# 8bitLineSensor.net
KiCad netlist of a schematic drawn in EAGLE
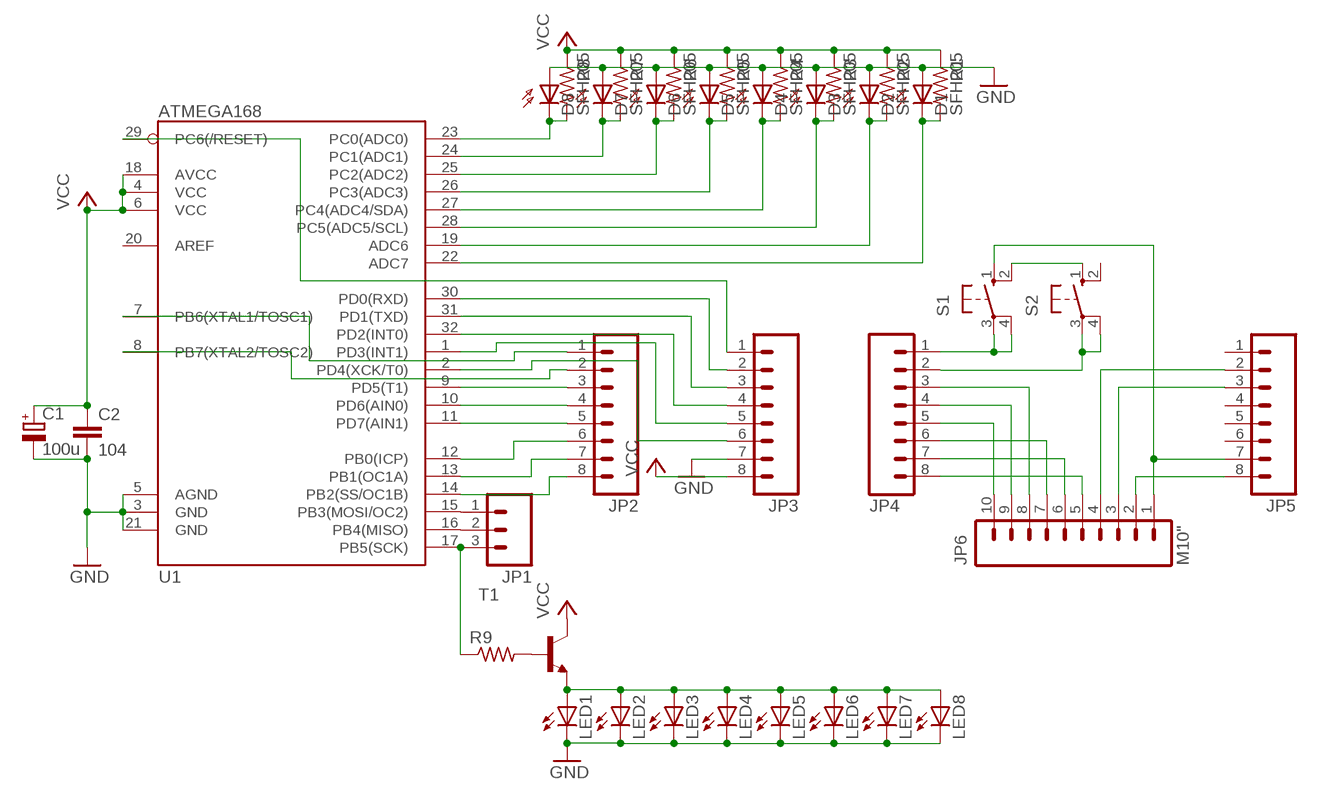
[diagram p0: schematic, sheet 1]

(export (version "E")
  (design (tool "Eeschema 10.0.6"))
  (components
    (comp (ref "C1")
      (value "100u")
      (footprint "eagle-import:E2,5-7")
      (libsource (lib "eagle-import") (part "CPOL-EUE2.5-7"))
    )
    (comp (ref "C2")
      (value "104")
      (footprint "eagle-import:C0805")
      (libsource (lib "eagle-import") (part "C-EUC0805"))
    )
    (comp (ref "D1")
      (value "SFH205")
      (footprint "eagle-import:SFH205")
      (libsource (lib "eagle-import") (part "SFH205"))
    )
    (comp (ref "D2")
      (value "SFH205")
      (footprint "eagle-import:SFH205")
      (libsource (lib "eagle-import") (part "SFH205"))
    )
    (comp (ref "D3")
      (value "SFH205")
      (footprint "eagle-import:SFH205")
      (libsource (lib "eagle-import") (part "SFH205"))
    )
    (comp (ref "D4")
      (value "SFH205")
      (footprint "eagle-import:SFH205")
      (libsource (lib "eagle-import") (part "SFH205"))
    )
    (comp (ref "D5")
      (value "SFH205")
      (footprint "eagle-import:SFH205")
      (libsource (lib "eagle-import") (part "SFH205"))
    )
    (comp (ref "D6")
      (value "SFH205")
      (footprint "eagle-import:SFH205")
      (libsource (lib "eagle-import") (part "SFH205"))
    )
    (comp (ref "D7")
      (value "SFH205")
      (footprint "eagle-import:SFH205")
      (libsource (lib "eagle-import") (part "SFH205"))
    )
    (comp (ref "D8")
      (value "SFH205")
      (footprint "eagle-import:SFH205")
      (libsource (lib "eagle-import") (part "SFH205"))
    )
    (comp (ref "JP1")
      (value "M03PTH")
      (footprint "eagle-import:1X03")
      (libsource (lib "eagle-import") (part "M03PTH"))
    )
    (comp (ref "JP2")
      (value "M08")
      (footprint "eagle-import:1X08")
      (libsource (lib "eagle-import") (part "M08"))
    )
    (comp (ref "JP3")
      (value "M08")
      (footprint "eagle-import:1X08")
      (libsource (lib "eagle-import") (part "M08"))
    )
    (comp (ref "JP4")
      (value "M08")
      (footprint "eagle-import:1X08")
      (libsource (lib "eagle-import") (part "M08"))
    )
    (comp (ref "JP5")
      (value "M08")
      (footprint "eagle-import:1X08")
      (libsource (lib "eagle-import") (part "M08"))
    )
    (comp (ref "JP6")
      (value "M10\"")
      (footprint "eagle-import:1X10")
      (libsource (lib "eagle-import") (part "M10{dblquote}"))
    )
    (comp (ref "LED1")
      (value "LED5MM")
      (footprint "eagle-import:LED5MM")
      (libsource (lib "eagle-import") (part "LED5MM"))
    )
    (comp (ref "LED2")
      (value "LED5MM")
      (footprint "eagle-import:LED5MM")
      (libsource (lib "eagle-import") (part "LED5MM"))
    )
    (comp (ref "LED3")
      (value "LED5MM")
      (footprint "eagle-import:LED5MM")
      (libsource (lib "eagle-import") (part "LED5MM"))
    )
    (comp (ref "LED4")
      (value "LED5MM")
      (footprint "eagle-import:LED5MM")
      (libsource (lib "eagle-import") (part "LED5MM"))
    )
    (comp (ref "LED5")
      (value "LED5MM")
      (footprint "eagle-import:LED5MM")
      (libsource (lib "eagle-import") (part "LED5MM"))
    )
    (comp (ref "LED6")
      (value "LED5MM")
      (footprint "eagle-import:LED5MM")
      (libsource (lib "eagle-import") (part "LED5MM"))
    )
    (comp (ref "LED7")
      (value "LED5MM")
      (footprint "eagle-import:LED5MM")
      (libsource (lib "eagle-import") (part "LED5MM"))
    )
    (comp (ref "LED8")
      (value "LED5MM")
      (footprint "eagle-import:LED5MM")
      (libsource (lib "eagle-import") (part "LED5MM"))
    )
    (comp (ref "R1")
      (value "R-US_R0805")
      (footprint "eagle-import:R0805")
      (libsource (lib "eagle-import") (part "R-US_R0805"))
    )
    (comp (ref "R2")
      (value "R-US_R0805")
      (footprint "eagle-import:R0805")
      (libsource (lib "eagle-import") (part "R-US_R0805"))
    )
    (comp (ref "R3")
      (value "R-US_R0805")
      (footprint "eagle-import:R0805")
      (libsource (lib "eagle-import") (part "R-US_R0805"))
    )
    (comp (ref "R4")
      (value "R-US_R0805")
      (footprint "eagle-import:R0805")
      (libsource (lib "eagle-import") (part "R-US_R0805"))
    )
    (comp (ref "R5")
      (value "R-US_R0805")
      (footprint "eagle-import:R0805")
      (libsource (lib "eagle-import") (part "R-US_R0805"))
    )
    (comp (ref "R6")
      (value "R-US_R0805")
      (footprint "eagle-import:R0805")
      (libsource (lib "eagle-import") (part "R-US_R0805"))
    )
    (comp (ref "R7")
      (value "R-US_R0805")
      (footprint "eagle-import:R0805")
      (libsource (lib "eagle-import") (part "R-US_R0805"))
    )
    (comp (ref "R8")
      (value "R-US_R0805")
      (footprint "eagle-import:R0805")
      (libsource (lib "eagle-import") (part "R-US_R0805"))
    )
    (comp (ref "R9")
      (value "R-US_R0805")
      (footprint "eagle-import:R0805")
      (libsource (lib "eagle-import") (part "R-US_R0805"))
    )
    (comp (ref "S1")
      (value "10-XX")
      (footprint "eagle-import:B3F-10XX")
      (fields (field (name "MPN") "B3F-1000"))
      (libsource (lib "eagle-import") (part "10-XX"))
    )
    (comp (ref "S2")
      (value "10-XX")
      (footprint "eagle-import:B3F-10XX")
      (fields (field (name "MPN") "B3F-1000"))
      (libsource (lib "eagle-import") (part "10-XX"))
    )
    (comp (ref "T1")
      (value "MMBT2222ALT1-NPN-SOT23-BEC")
      (footprint "eagle-import:SOT23-BEC")
      (libsource (lib "eagle-import") (part "-NPN-SOT23-BECMMBT2222ALT1"))
    )
    (comp (ref "U1")
      (value "ATMEGA168")
      (footprint "eagle-import:TQFP32-08")
      (libsource (lib "eagle-import") (part "ATMEGA168"))
    )
  )
  (nets
    (net (code "1") (name "GND") (class "Default")
      (node (ref "C1") (pin "-") (pinfunction "-_-") (pintype "passive"))
      (node (ref "C2") (pin "2") (pinfunction "2_2") (pintype "passive"))
      (node (ref "D1") (pin "A") (pinfunction "A_A") (pintype "passive"))
      (node (ref "D2") (pin "A") (pinfunction "A_A") (pintype "passive"))
      (node (ref "D3") (pin "A") (pinfunction "A_A") (pintype "passive"))
      (node (ref "D4") (pin "A") (pinfunction "A_A") (pintype "passive"))
      (node (ref "D5") (pin "A") (pinfunction "A_A") (pintype "passive"))
      (node (ref "D6") (pin "A") (pinfunction "A_A") (pintype "passive"))
      (node (ref "D7") (pin "A") (pinfunction "A_A") (pintype "passive"))
      (node (ref "D8") (pin "A") (pinfunction "A_A") (pintype "passive"))
      (node (ref "JP3") (pin "7") (pinfunction "7_7") (pintype "passive"))
      (node (ref "LED1") (pin "K") (pinfunction "C_K") (pintype "passive"))
      (node (ref "LED2") (pin "K") (pinfunction "C_K") (pintype "passive"))
      (node (ref "LED3") (pin "K") (pinfunction "C_K") (pintype "passive"))
      (node (ref "LED4") (pin "K") (pinfunction "C_K") (pintype "passive"))
      (node (ref "LED5") (pin "K") (pinfunction "C_K") (pintype "passive"))
      (node (ref "LED6") (pin "K") (pinfunction "C_K") (pintype "passive"))
      (node (ref "LED7") (pin "K") (pinfunction "C_K") (pintype "passive"))
      (node (ref "LED8") (pin "K") (pinfunction "C_K") (pintype "passive"))
      (node (ref "U1") (pin "21") (pinfunction "GND_21") (pintype "bidirectional"))
      (node (ref "U1") (pin "3") (pinfunction "GND_3") (pintype "bidirectional"))
      (node (ref "U1") (pin "5") (pinfunction "AGND_5") (pintype "bidirectional"))
    )
    (net (code "2") (name "Net-(D1-C)") (class "Default")
      (node (ref "D1") (pin "K") (pinfunction "C_K") (pintype "passive"))
      (node (ref "R1") (pin "2") (pinfunction "2_2") (pintype "passive"))
      (node (ref "U1") (pin "22") (pinfunction "ADC7_22") (pintype "bidirectional"))
    )
    (net (code "3") (name "Net-(D2-C)") (class "Default")
      (node (ref "D2") (pin "K") (pinfunction "C_K") (pintype "passive"))
      (node (ref "R2") (pin "2") (pinfunction "2_2") (pintype "passive"))
      (node (ref "U1") (pin "19") (pinfunction "ADC6_19") (pintype "bidirectional"))
    )
    (net (code "4") (name "Net-(D3-C)") (class "Default")
      (node (ref "D3") (pin "K") (pinfunction "C_K") (pintype "passive"))
      (node (ref "R3") (pin "2") (pinfunction "2_2") (pintype "passive"))
      (node (ref "U1") (pin "28") (pinfunction "PC5(ADC5/SCL)_28") (pintype "bidirectional"))
    )
    (net (code "5") (name "Net-(D4-C)") (class "Default")
      (node (ref "D4") (pin "K") (pinfunction "C_K") (pintype "passive"))
      (node (ref "R4") (pin "2") (pinfunction "2_2") (pintype "passive"))
      (node (ref "U1") (pin "27") (pinfunction "PC4(ADC4/SDA)_27") (pintype "bidirectional"))
    )
    (net (code "6") (name "Net-(D5-C)") (class "Default")
      (node (ref "D5") (pin "K") (pinfunction "C_K") (pintype "passive"))
      (node (ref "R5") (pin "2") (pinfunction "2_2") (pintype "passive"))
      (node (ref "U1") (pin "26") (pinfunction "PC3(ADC3)_26") (pintype "bidirectional"))
    )
    (net (code "7") (name "Net-(D6-C)") (class "Default")
      (node (ref "D6") (pin "K") (pinfunction "C_K") (pintype "passive"))
      (node (ref "R6") (pin "2") (pinfunction "2_2") (pintype "passive"))
      (node (ref "U1") (pin "25") (pinfunction "PC2(ADC2)_25") (pintype "bidirectional"))
    )
    (net (code "8") (name "Net-(D7-C)") (class "Default")
      (node (ref "D7") (pin "K") (pinfunction "C_K") (pintype "passive"))
      (node (ref "R7") (pin "2") (pinfunction "2_2") (pintype "passive"))
      (node (ref "U1") (pin "24") (pinfunction "PC1(ADC1)_24") (pintype "bidirectional"))
    )
    (net (code "9") (name "Net-(D8-C)") (class "Default")
      (node (ref "D8") (pin "K") (pinfunction "C_K") (pintype "passive"))
      (node (ref "R8") (pin "2") (pinfunction "2_2") (pintype "passive"))
      (node (ref "U1") (pin "23") (pinfunction "PC0(ADC0)_23") (pintype "bidirectional"))
    )
    (net (code "10") (name "Net-(JP4-Pad3)") (class "Default")
      (node (ref "JP4") (pin "3") (pinfunction "3_3") (pintype "passive"))
      (node (ref "JP6") (pin "8") (pinfunction "8_8") (pintype "passive"))
    )
    (net (code "11") (name "Net-(JP4-Pad4)") (class "Default")
      (node (ref "JP4") (pin "4") (pinfunction "4_4") (pintype "passive"))
      (node (ref "JP6") (pin "9") (pinfunction "9_9") (pintype "passive"))
    )
    (net (code "12") (name "Net-(JP4-Pad5)") (class "Default")
      (node (ref "JP4") (pin "5") (pinfunction "5_5") (pintype "passive"))
      (node (ref "JP6") (pin "10") (pinfunction "10_10") (pintype "passive"))
    )
    (net (code "13") (name "Net-(JP4-Pad6)") (class "Default")
      (node (ref "JP4") (pin "6") (pinfunction "6_6") (pintype "passive"))
      (node (ref "JP6") (pin "7") (pinfunction "7_7") (pintype "passive"))
    )
    (net (code "14") (name "Net-(JP4-Pad7)") (class "Default")
      (node (ref "JP4") (pin "7") (pinfunction "7_7") (pintype "passive"))
      (node (ref "JP6") (pin "6") (pinfunction "6_6") (pintype "passive"))
    )
    (net (code "15") (name "Net-(JP4-Pad8)") (class "Default")
      (node (ref "JP4") (pin "8") (pinfunction "8_8") (pintype "passive"))
      (node (ref "JP6") (pin "5") (pinfunction "5_5") (pintype "passive"))
    )
    (net (code "16") (name "Net-(JP5-Pad2)") (class "Default")
      (node (ref "JP5") (pin "2") (pinfunction "2_2") (pintype "passive"))
      (node (ref "JP6") (pin "4") (pinfunction "4_4") (pintype "passive"))
    )
    (net (code "17") (name "Net-(JP5-Pad3)") (class "Default")
      (node (ref "JP5") (pin "3") (pinfunction "3_3") (pintype "passive"))
      (node (ref "JP6") (pin "3") (pinfunction "3_3") (pintype "passive"))
    )
    (net (code "18") (name "Net-(JP5-Pad8)") (class "Default")
      (node (ref "JP5") (pin "8") (pinfunction "8_8") (pintype "passive"))
      (node (ref "JP6") (pin "2") (pinfunction "2_2") (pintype "passive"))
    )
    (net (code "19") (name "Net-(LED1-PadA)") (class "Default")
      (node (ref "LED1") (pin "A") (pinfunction "A_A") (pintype "passive"))
      (node (ref "LED2") (pin "A") (pinfunction "A_A") (pintype "passive"))
      (node (ref "LED3") (pin "A") (pinfunction "A_A") (pintype "passive"))
      (node (ref "LED4") (pin "A") (pinfunction "A_A") (pintype "passive"))
      (node (ref "LED5") (pin "A") (pinfunction "A_A") (pintype "passive"))
      (node (ref "LED6") (pin "A") (pinfunction "A_A") (pintype "passive"))
      (node (ref "LED7") (pin "A") (pinfunction "A_A") (pintype "passive"))
      (node (ref "LED8") (pin "A") (pinfunction "A_A") (pintype "passive"))
      (node (ref "T1") (pin "E") (pinfunction "E_E") (pintype "passive"))
    )
    (net (code "20") (name "Net-(R9-Pad2)") (class "Default")
      (node (ref "R9") (pin "2") (pinfunction "2_2") (pintype "passive"))
      (node (ref "T1") (pin "B") (pinfunction "B_B") (pintype "passive"))
    )
    (net (code "21") (name "Net-(S1-P)") (class "Default")
      (node (ref "JP4") (pin "1") (pinfunction "1_1") (pintype "passive"))
      (node (ref "S1") (pin "3") (pinfunction "P_3") (pintype "passive"))
      (node (ref "S1") (pin "4") (pinfunction "P1_4") (pintype "passive"))
    )
    (net (code "22") (name "Net-(S1-S)") (class "Default")
      (node (ref "JP5") (pin "7") (pinfunction "7_7") (pintype "passive"))
      (node (ref "JP6") (pin "1") (pinfunction "1_1") (pintype "passive"))
      (node (ref "S1") (pin "1") (pinfunction "S_1") (pintype "passive"))
    )
    (net (code "23") (name "Net-(S1-S1)") (class "Default")
      (node (ref "S1") (pin "2") (pinfunction "S1_2") (pintype "passive"))
      (node (ref "S2") (pin "1") (pinfunction "S_1") (pintype "passive"))
    )
    (net (code "24") (name "Net-(S2-P)") (class "Default")
      (node (ref "JP4") (pin "2") (pinfunction "2_2") (pintype "passive"))
      (node (ref "S2") (pin "3") (pinfunction "P_3") (pintype "passive"))
      (node (ref "S2") (pin "4") (pinfunction "P1_4") (pintype "passive"))
    )
    (net (code "25") (name "Net-(U1-PB0(ICP))") (class "Default")
      (node (ref "JP2") (pin "6") (pinfunction "6_6") (pintype "passive"))
      (node (ref "U1") (pin "12") (pinfunction "PB0(ICP)_12") (pintype "bidirectional"))
    )
    (net (code "26") (name "Net-(U1-PB1(OC1A))") (class "Default")
      (node (ref "JP2") (pin "7") (pinfunction "7_7") (pintype "passive"))
      (node (ref "U1") (pin "13") (pinfunction "PB1(OC1A)_13") (pintype "bidirectional"))
    )
    (net (code "27") (name "Net-(U1-PB2(SS{slash}OC1B))") (class "Default")
      (node (ref "JP2") (pin "8") (pinfunction "8_8") (pintype "passive"))
      (node (ref "U1") (pin "14") (pinfunction "PB2(SS/OC1B)_14") (pintype "bidirectional"))
    )
    (net (code "28") (name "Net-(U1-PB3(MOSI{slash}OC2))") (class "Default")
      (node (ref "JP1") (pin "1") (pinfunction "1_1") (pintype "passive"))
      (node (ref "U1") (pin "15") (pinfunction "PB3(MOSI/OC2)_15") (pintype "bidirectional"))
    )
    (net (code "29") (name "Net-(U1-PB4(MISO))") (class "Default")
      (node (ref "JP1") (pin "2") (pinfunction "2_2") (pintype "passive"))
      (node (ref "U1") (pin "16") (pinfunction "PB4(MISO)_16") (pintype "bidirectional"))
    )
    (net (code "30") (name "Net-(U1-PB5(SCK))") (class "Default")
      (node (ref "JP1") (pin "3") (pinfunction "3_3") (pintype "passive"))
      (node (ref "R9") (pin "1") (pinfunction "1_1") (pintype "passive"))
      (node (ref "U1") (pin "17") (pinfunction "PB5(SCK)_17") (pintype "bidirectional"))
    )
    (net (code "31") (name "Net-(U1-PB6(XTAL1{slash}TOSC1))") (class "Default")
      (node (ref "JP2") (pin "1") (pinfunction "1_1") (pintype "passive"))
      (node (ref "U1") (pin "7") (pinfunction "PB6(XTAL1/TOSC1)_7") (pintype "bidirectional"))
    )
    (net (code "32") (name "Net-(U1-PB7(XTAL2{slash}TOSC2))") (class "Default")
      (node (ref "JP2") (pin "2") (pinfunction "2_2") (pintype "passive"))
      (node (ref "U1") (pin "8") (pinfunction "PB7(XTAL2/TOSC2)_8") (pintype "bidirectional"))
    )
    (net (code "33") (name "Net-(U1-PC6({slash}RESET))") (class "Default")
      (node (ref "JP3") (pin "1") (pinfunction "1_1") (pintype "passive"))
      (node (ref "U1") (pin "29") (pinfunction "PC6(/RESET)_29") (pintype "bidirectional"))
    )
    (net (code "34") (name "Net-(U1-PD0(RXD))") (class "Default")
      (node (ref "JP3") (pin "2") (pinfunction "2_2") (pintype "passive"))
      (node (ref "U1") (pin "30") (pinfunction "PD0(RXD)_30") (pintype "bidirectional"))
    )
    (net (code "35") (name "Net-(U1-PD1(TXD))") (class "Default")
      (node (ref "JP3") (pin "3") (pinfunction "3_3") (pintype "passive"))
      (node (ref "U1") (pin "31") (pinfunction "PD1(TXD)_31") (pintype "bidirectional"))
    )
    (net (code "36") (name "Net-(U1-PD2(INT0))") (class "Default")
      (node (ref "JP3") (pin "4") (pinfunction "4_4") (pintype "passive"))
      (node (ref "U1") (pin "32") (pinfunction "PD2(INT0)_32") (pintype "bidirectional"))
    )
    (net (code "37") (name "Net-(U1-PD3(INT1))") (class "Default")
      (node (ref "JP3") (pin "5") (pinfunction "5_5") (pintype "passive"))
      (node (ref "U1") (pin "1") (pinfunction "PD3(INT1)_1") (pintype "bidirectional"))
    )
    (net (code "38") (name "Net-(U1-PD4(XCK{slash}T0))") (class "Default")
      (node (ref "JP3") (pin "6") (pinfunction "6_6") (pintype "passive"))
      (node (ref "U1") (pin "2") (pinfunction "PD4(XCK/T0)_2") (pintype "bidirectional"))
    )
    (net (code "39") (name "Net-(U1-PD5(T1))") (class "Default")
      (node (ref "JP2") (pin "3") (pinfunction "3_3") (pintype "passive"))
      (node (ref "U1") (pin "9") (pinfunction "PD5(T1)_9") (pintype "bidirectional"))
    )
    (net (code "40") (name "Net-(U1-PD6(AIN0))") (class "Default")
      (node (ref "JP2") (pin "4") (pinfunction "4_4") (pintype "passive"))
      (node (ref "U1") (pin "10") (pinfunction "PD6(AIN0)_10") (pintype "bidirectional"))
    )
    (net (code "41") (name "Net-(U1-PD7(AIN1))") (class "Default")
      (node (ref "JP2") (pin "5") (pinfunction "5_5") (pintype "passive"))
      (node (ref "U1") (pin "11") (pinfunction "PD7(AIN1)_11") (pintype "bidirectional"))
    )
    (net (code "42") (name "VCC") (class "Default")
      (node (ref "C1") (pin "+") (pinfunction "+_+") (pintype "passive"))
      (node (ref "C2") (pin "1") (pinfunction "1_1") (pintype "passive"))
      (node (ref "JP3") (pin "8") (pinfunction "8_8") (pintype "passive"))
      (node (ref "R1") (pin "1") (pinfunction "1_1") (pintype "passive"))
      (node (ref "R2") (pin "1") (pinfunction "1_1") (pintype "passive"))
      (node (ref "R3") (pin "1") (pinfunction "1_1") (pintype "passive"))
      (node (ref "R4") (pin "1") (pinfunction "1_1") (pintype "passive"))
      (node (ref "R5") (pin "1") (pinfunction "1_1") (pintype "passive"))
      (node (ref "R6") (pin "1") (pinfunction "1_1") (pintype "passive"))
      (node (ref "R7") (pin "1") (pinfunction "1_1") (pintype "passive"))
      (node (ref "R8") (pin "1") (pinfunction "1_1") (pintype "passive"))
      (node (ref "T1") (pin "C") (pinfunction "C_C") (pintype "passive"))
      (node (ref "U1") (pin "18") (pinfunction "AVCC_18") (pintype "bidirectional"))
      (node (ref "U1") (pin "4") (pinfunction "VCC_4") (pintype "bidirectional"))
      (node (ref "U1") (pin "6") (pinfunction "VCC_6") (pintype "bidirectional"))
    )
    (net (code "43") (name "unconnected-(JP5-Pad1)") (class "Default")
      (node (ref "JP5") (pin "1") (pinfunction "1_1") (pintype "passive"))
    )
    (net (code "44") (name "unconnected-(JP5-Pad4)") (class "Default")
      (node (ref "JP5") (pin "4") (pinfunction "4_4") (pintype "passive"))
    )
    (net (code "45") (name "unconnected-(JP5-Pad5)") (class "Default")
      (node (ref "JP5") (pin "5") (pinfunction "5_5") (pintype "passive"))
    )
    (net (code "46") (name "unconnected-(JP5-Pad6)") (class "Default")
      (node (ref "JP5") (pin "6") (pinfunction "6_6") (pintype "passive"))
    )
    (net (code "47") (name "unconnected-(S2-S1-Pad2)") (class "Default")
      (node (ref "S2") (pin "2") (pinfunction "S1_2") (pintype "passive"))
    )
    (net (code "48") (name "unconnected-(U1-AREF-Pad20)") (class "Default")
      (node (ref "U1") (pin "20") (pinfunction "AREF_20") (pintype "bidirectional"))
    )
  )
)
